# Sheet1.net
KiCad netlist of a schematic drawn in Altium Designer
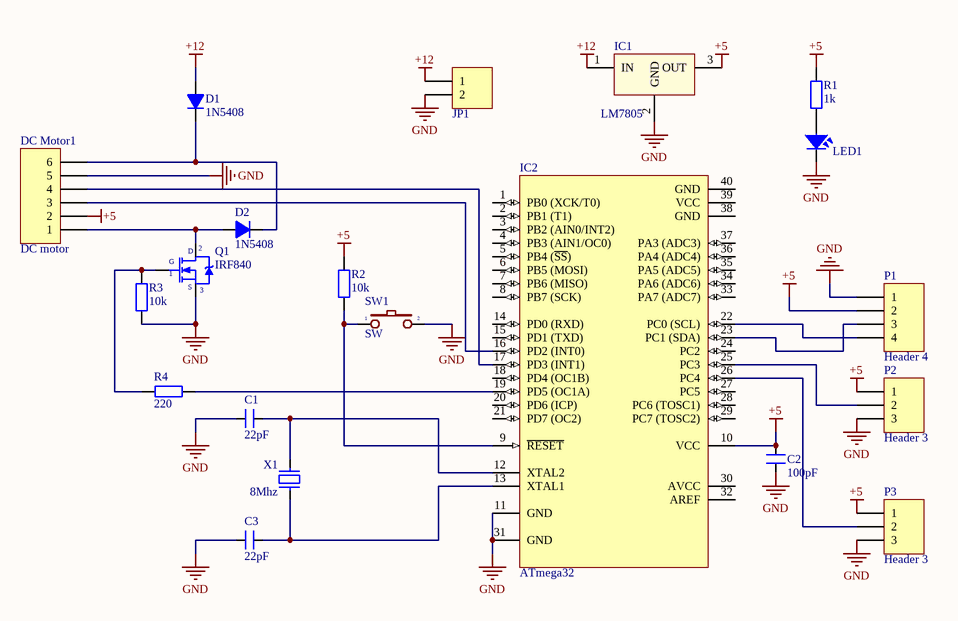
[diagram p0: Sheet1.SchDoc]

(export (version "E")
  (design (tool "Eeschema 10.0.6"))
  (components
    (comp (ref "C1")
      (value "22pF")
      (footprint "CN1")
      (description "Cap np  1pF - 472pF")
      (libsource (lib "Thuvien3D") (part "CN1"))
    )
    (comp (ref "C2")
      (value "100pF")
      (footprint "CN1")
      (description "Cap np  1pF - 472pF")
      (libsource (lib "Thuvien3D") (part "CN1"))
    )
    (comp (ref "C3")
      (value "22pF")
      (footprint "CN1")
      (description "Cap np  1pF - 472pF")
      (libsource (lib "Thuvien3D") (part "CN1"))
    )
    (comp (ref "D1")
      (value "1N5408")
      (footprint "D5A")
      (description "Diode 5A")
      (libsource (lib "Thuvien3D") (part "D5A"))
    )
    (comp (ref "D2")
      (value "1N5408")
      (footprint "D5A")
      (description "Diode 5A")
      (libsource (lib "Thuvien3D") (part "D5A"))
    )
    (comp (ref "DC Motor1")
      (value "DC motor")
      (footprint "HDR1X6")
      (description "Header, 6-Pin")
      (fields (field (name "PUBLISHER") "Altium Limited"))
      (libsource (lib "Miscellaneous Connectors") (part "Header 6"))
    )
    (comp (ref "IC1")
      (value "LM7805")
      (footprint "QTO-220")
      (description "On ap +, from + 5 to + 24VDC")
      (libsource (lib "Thuvien3D") (part "LM78xx"))
    )
    (comp (ref "IC2")
      (value "ATmega32")
      (footprint "DIP40/W0.6")
      (description "8-Bit AVR Microcontroller with 8K Bytes of In-System Programmable Flash Memory")
      (libsource (lib "Thuvien3D") (part "ATmega8535"))
    )
    (comp (ref "JP1")
      (value "Header 2_1")
      (footprint "HED2")
      (description "Header, 2-Pin")
      (fields (field (name "MANUFACTURER") "Generic Components"))
      (libsource (lib "Thuvien3D") (part "Header 2_1"))
    )
    (comp (ref "LED1")
      (value "LED")
      (footprint "LED-3")
      (description "LED Single colour Green and Red")
      (libsource (lib "Thuvien3D") (part "LED"))
    )
    (comp (ref "P1")
      (value "Header 4")
      (footprint "HDR1X4")
      (description "Header, 4-Pin")
      (fields (field (name "PUBLISHER") "Altium Limited"))
      (libsource (lib "Miscellaneous Connectors") (part "Header 4"))
    )
    (comp (ref "P2")
      (value "Header 3")
      (footprint "HDR1X3")
      (description "Header, 3-Pin")
      (fields (field (name "PUBLISHER") "Altium Limited"))
      (libsource (lib "Miscellaneous Connectors") (part "Header 3"))
    )
    (comp (ref "P3")
      (value "Header 3")
      (footprint "HDR1X3")
      (description "Header, 3-Pin")
      (fields (field (name "PUBLISHER") "Altium Limited"))
      (libsource (lib "Miscellaneous Connectors") (part "Header 3"))
    )
    (comp (ref "Q1")
      (value "IRF840")
      (footprint "QTO-220")
      (description "MOSFET N - CHANNEL 500V - 0.75 - 8A - TO-220")
      (libsource (lib "Thuvien3D") (part "IRF840"))
    )
    (comp (ref "R1")
      (value "1k")
      (footprint "R1/4W")
      (description "Resistor 1/4W")
      (libsource (lib "Thuvien3D") (part "R1/4W"))
    )
    (comp (ref "R2")
      (value "10k")
      (footprint "R1/4W")
      (description "Resistor 1/4W")
      (libsource (lib "Thuvien3D") (part "R1/4W"))
    )
    (comp (ref "R3")
      (value "10k")
      (footprint "R1/4W")
      (description "Resistor 1/4W")
      (libsource (lib "Thuvien3D") (part "R1/4W"))
    )
    (comp (ref "R4")
      (value "220")
      (footprint "R1/4W")
      (description "Resistor 1/4W")
      (libsource (lib "Thuvien3D") (part "R1/4W"))
    )
    (comp (ref "SW1")
      (value "SW")
      (footprint "SW2")
      (description "Switch button 2 pin")
      (libsource (lib "Thuvien3D") (part "SW2"))
    )
    (comp (ref "X1")
      (value "8Mhz")
      (footprint "XT2")
      (description "Crystal For all Crystal 2pin.")
      (libsource (lib "Thuvien3D") (part "XT2"))
    )
  )
  (nets
    (net (code "1") (name "+5") (class "Default")
      (node (ref "C2") (pin "2") (pinfunction "2_2") (pintype "passive"))
      (node (ref "DC Motor1") (pin "2") (pinfunction "2_2") (pintype "passive"))
      (node (ref "IC1") (pin "3") (pinfunction "OUT_3") (pintype "passive"))
      (node (ref "IC2") (pin "10") (pinfunction "VCC_10") (pintype "power_in"))
      (node (ref "P1") (pin "2") (pinfunction "2_2") (pintype "passive"))
      (node (ref "P2") (pin "1") (pinfunction "1_1") (pintype "passive"))
      (node (ref "P3") (pin "1") (pinfunction "1_1") (pintype "passive"))
      (node (ref "R1") (pin "2") (pinfunction "2_2") (pintype "passive"))
      (node (ref "R2") (pin "2") (pinfunction "2_2") (pintype "passive"))
    )
    (net (code "2") (name "+12") (class "Default")
      (node (ref "D1") (pin "1") (pinfunction "A_1") (pintype "passive"))
      (node (ref "IC1") (pin "1") (pinfunction "IN_1") (pintype "passive"))
      (node (ref "JP1") (pin "1") (pinfunction "1_1") (pintype "passive"))
    )
    (net (code "3") (name "GND") (class "Default")
      (node (ref "C1") (pin "1") (pinfunction "1_1") (pintype "passive"))
      (node (ref "C2") (pin "1") (pinfunction "1_1") (pintype "passive"))
      (node (ref "C3") (pin "1") (pinfunction "1_1") (pintype "passive"))
      (node (ref "DC Motor1") (pin "5") (pinfunction "5_5") (pintype "passive"))
      (node (ref "IC1") (pin "2") (pinfunction "GND_2") (pintype "passive"))
      (node (ref "IC2") (pin "11") (pinfunction "GND_11") (pintype "power_in"))
      (node (ref "IC2") (pin "31") (pinfunction "GND_31") (pintype "power_in"))
      (node (ref "JP1") (pin "2") (pinfunction "2_2") (pintype "passive"))
      (node (ref "LED1") (pin "2") (pinfunction "2_2") (pintype "passive"))
      (node (ref "P1") (pin "1") (pinfunction "1_1") (pintype "passive"))
      (node (ref "P2") (pin "3") (pinfunction "3_3") (pintype "passive"))
      (node (ref "P3") (pin "3") (pinfunction "3_3") (pintype "passive"))
      (node (ref "Q1") (pin "3") (pinfunction "S_3") (pintype "passive"))
      (node (ref "R3") (pin "1") (pinfunction "1_1") (pintype "passive"))
      (node (ref "SW1") (pin "2") (pinfunction "2_2") (pintype "passive"))
    )
    (net (code "4") (name "Net-(D1-K)") (class "Default")
      (node (ref "D1") (pin "2") (pinfunction "K_2") (pintype "passive"))
      (node (ref "D2") (pin "2") (pinfunction "K_2") (pintype "passive"))
      (node (ref "DC Motor1") (pin "6") (pinfunction "6_6") (pintype "passive"))
    )
    (net (code "5") (name "Net-(D2-A)") (class "Default")
      (node (ref "D2") (pin "1") (pinfunction "A_1") (pintype "passive"))
      (node (ref "DC Motor1") (pin "1") (pinfunction "1_1") (pintype "passive"))
      (node (ref "Q1") (pin "2") (pinfunction "D_2") (pintype "passive"))
    )
    (net (code "6") (name "Net-(IC2-PC0_(SCL))") (class "Default")
      (node (ref "IC2") (pin "22") (pinfunction "PC0_(SCL)_22") (pintype "bidirectional"))
      (node (ref "P1") (pin "4") (pinfunction "4_4") (pintype "passive"))
    )
    (net (code "7") (name "Net-(IC2-PC1_(SDA))") (class "Default")
      (node (ref "IC2") (pin "23") (pinfunction "PC1_(SDA)_23") (pintype "bidirectional"))
      (node (ref "P1") (pin "3") (pinfunction "3_3") (pintype "passive"))
    )
    (net (code "8") (name "Net-(IC2-PC3)") (class "Default")
      (node (ref "IC2") (pin "25") (pinfunction "PC3_25") (pintype "bidirectional"))
      (node (ref "P2") (pin "2") (pinfunction "2_2") (pintype "passive"))
    )
    (net (code "9") (name "Net-(IC2-PC4)") (class "Default")
      (node (ref "IC2") (pin "26") (pinfunction "PC4_26") (pintype "bidirectional"))
      (node (ref "P3") (pin "2") (pinfunction "2_2") (pintype "passive"))
    )
    (net (code "10") (name "Net-(IC2-PD2_(INT0))") (class "Default")
      (node (ref "DC Motor1") (pin "3") (pinfunction "3_3") (pintype "passive"))
      (node (ref "IC2") (pin "16") (pinfunction "PD2_(INT0)_16") (pintype "bidirectional"))
    )
    (net (code "11") (name "Net-(IC2-PD3_(INT1))") (class "Default")
      (node (ref "DC Motor1") (pin "4") (pinfunction "4_4") (pintype "passive"))
      (node (ref "IC2") (pin "17") (pinfunction "PD3_(INT1)_17") (pintype "bidirectional"))
    )
    (net (code "12") (name "Net-(IC2-PD5_(OC1A))") (class "Default")
      (node (ref "IC2") (pin "19") (pinfunction "PD5_(OC1A)_19") (pintype "bidirectional"))
      (node (ref "R4") (pin "2") (pinfunction "2_2") (pintype "passive"))
    )
    (net (code "13") (name "Net-(IC2-XTAL1)") (class "Default")
      (node (ref "C3") (pin "2") (pinfunction "2_2") (pintype "passive"))
      (node (ref "IC2") (pin "13") (pinfunction "XTAL1_13") (pintype "passive"))
      (node (ref "X1") (pin "2") (pinfunction "2_2") (pintype "passive"))
    )
    (net (code "14") (name "Net-(IC2-XTAL2)") (class "Default")
      (node (ref "C1") (pin "2") (pinfunction "2_2") (pintype "passive"))
      (node (ref "IC2") (pin "12") (pinfunction "XTAL2_12") (pintype "passive"))
      (node (ref "X1") (pin "1") (pinfunction "1_1") (pintype "passive"))
    )
    (net (code "15") (name "Net-(IC2-~{RESET})") (class "Default")
      (node (ref "IC2") (pin "9") (pinfunction "~{RESET}_9") (pintype "input"))
      (node (ref "R2") (pin "1") (pinfunction "1_1") (pintype "passive"))
      (node (ref "SW1") (pin "1") (pinfunction "1_1") (pintype "passive"))
    )
    (net (code "16") (name "Net-(LED1-Pad1)") (class "Default")
      (node (ref "LED1") (pin "1") (pinfunction "1_1") (pintype "passive"))
      (node (ref "R1") (pin "1") (pinfunction "1_1") (pintype "passive"))
    )
    (net (code "17") (name "Net-(Q1-G)") (class "Default")
      (node (ref "Q1") (pin "1") (pinfunction "G_1") (pintype "passive"))
      (node (ref "R3") (pin "2") (pinfunction "2_2") (pintype "passive"))
      (node (ref "R4") (pin "1") (pinfunction "1_1") (pintype "passive"))
    )
    (net (code "18") (name "unconnected-(IC2-AREF-Pad32)") (class "Default")
      (node (ref "IC2") (pin "32") (pinfunction "AREF_32") (pintype "passive"))
    )
    (net (code "19") (name "unconnected-(IC2-AVCC-Pad30)") (class "Default")
      (node (ref "IC2") (pin "30") (pinfunction "AVCC_30") (pintype "power_in"))
    )
    (net (code "20") (name "unconnected-(IC2-GND-Pad38)") (class "Default")
      (node (ref "IC2") (pin "38") (pinfunction "GND_38") (pintype "power_in"))
    )
    (net (code "21") (name "unconnected-(IC2-GND-Pad40)") (class "Default")
      (node (ref "IC2") (pin "40") (pinfunction "GND_40") (pintype "power_in"))
    )
    (net (code "22") (name "unconnected-(IC2-PA3_(ADC3)-Pad37)") (class "Default")
      (node (ref "IC2") (pin "37") (pinfunction "PA3_(ADC3)_37") (pintype "bidirectional"))
    )
    (net (code "23") (name "unconnected-(IC2-PA4_(ADC4)-Pad36)") (class "Default")
      (node (ref "IC2") (pin "36") (pinfunction "PA4_(ADC4)_36") (pintype "bidirectional"))
    )
    (net (code "24") (name "unconnected-(IC2-PA5_(ADC5)-Pad35)") (class "Default")
      (node (ref "IC2") (pin "35") (pinfunction "PA5_(ADC5)_35") (pintype "bidirectional"))
    )
    (net (code "25") (name "unconnected-(IC2-PA6_(ADC6)-Pad34)") (class "Default")
      (node (ref "IC2") (pin "34") (pinfunction "PA6_(ADC6)_34") (pintype "bidirectional"))
    )
    (net (code "26") (name "unconnected-(IC2-PA7_(ADC7)-Pad33)") (class "Default")
      (node (ref "IC2") (pin "33") (pinfunction "PA7_(ADC7)_33") (pintype "bidirectional"))
    )
    (net (code "27") (name "unconnected-(IC2-PB0_(XCK{slash}T0)-Pad1)") (class "Default")
      (node (ref "IC2") (pin "1") (pinfunction "PB0_(XCK/T0)_1") (pintype "bidirectional"))
    )
    (net (code "28") (name "unconnected-(IC2-PB1_(T1)-Pad2)") (class "Default")
      (node (ref "IC2") (pin "2") (pinfunction "PB1_(T1)_2") (pintype "bidirectional"))
    )
    (net (code "29") (name "unconnected-(IC2-PB2_(AIN0{slash}INT2)-Pad3)") (class "Default")
      (node (ref "IC2") (pin "3") (pinfunction "PB2_(AIN0/INT2)_3") (pintype "bidirectional"))
    )
    (net (code "30") (name "unconnected-(IC2-PB3_(AIN1{slash}OC0)-Pad4)") (class "Default")
      (node (ref "IC2") (pin "4") (pinfunction "PB3_(AIN1/OC0)_4") (pintype "bidirectional"))
    )
    (net (code "31") (name "unconnected-(IC2-PB4_(~{SS})-Pad5)") (class "Default")
      (node (ref "IC2") (pin "5") (pinfunction "PB4_(~{SS})_5") (pintype "bidirectional"))
    )
    (net (code "32") (name "unconnected-(IC2-PB5_(MOSI)-Pad6)") (class "Default")
      (node (ref "IC2") (pin "6") (pinfunction "PB5_(MOSI)_6") (pintype "bidirectional"))
    )
    (net (code "33") (name "unconnected-(IC2-PB6_(MISO)-Pad7)") (class "Default")
      (node (ref "IC2") (pin "7") (pinfunction "PB6_(MISO)_7") (pintype "bidirectional"))
    )
    (net (code "34") (name "unconnected-(IC2-PB7_(SCK)-Pad8)") (class "Default")
      (node (ref "IC2") (pin "8") (pinfunction "PB7_(SCK)_8") (pintype "bidirectional"))
    )
    (net (code "35") (name "unconnected-(IC2-PC2-Pad24)") (class "Default")
      (node (ref "IC2") (pin "24") (pinfunction "PC2_24") (pintype "bidirectional"))
    )
    (net (code "36") (name "unconnected-(IC2-PC5-Pad27)") (class "Default")
      (node (ref "IC2") (pin "27") (pinfunction "PC5_27") (pintype "bidirectional"))
    )
    (net (code "37") (name "unconnected-(IC2-PC6_(TOSC1)-Pad28)") (class "Default")
      (node (ref "IC2") (pin "28") (pinfunction "PC6_(TOSC1)_28") (pintype "bidirectional"))
    )
    (net (code "38") (name "unconnected-(IC2-PC7_(TOSC2)-Pad29)") (class "Default")
      (node (ref "IC2") (pin "29") (pinfunction "PC7_(TOSC2)_29") (pintype "bidirectional"))
    )
    (net (code "39") (name "unconnected-(IC2-PD0_(RXD)-Pad14)") (class "Default")
      (node (ref "IC2") (pin "14") (pinfunction "PD0_(RXD)_14") (pintype "bidirectional"))
    )
    (net (code "40") (name "unconnected-(IC2-PD1_(TXD)-Pad15)") (class "Default")
      (node (ref "IC2") (pin "15") (pinfunction "PD1_(TXD)_15") (pintype "bidirectional"))
    )
    (net (code "41") (name "unconnected-(IC2-PD4_(OC1B)-Pad18)") (class "Default")
      (node (ref "IC2") (pin "18") (pinfunction "PD4_(OC1B)_18") (pintype "bidirectional"))
    )
    (net (code "42") (name "unconnected-(IC2-PD6_(ICP)-Pad20)") (class "Default")
      (node (ref "IC2") (pin "20") (pinfunction "PD6_(ICP)_20") (pintype "bidirectional"))
    )
    (net (code "43") (name "unconnected-(IC2-PD7_(OC2)-Pad21)") (class "Default")
      (node (ref "IC2") (pin "21") (pinfunction "PD7_(OC2)_21") (pintype "bidirectional"))
    )
    (net (code "44") (name "unconnected-(IC2-VCC-Pad39)") (class "Default")
      (node (ref "IC2") (pin "39") (pinfunction "VCC_39") (pintype "power_in"))
    )
  )
)
